# NinjaPCR-PowerSupply.net
KiCad netlist of a schematic drawn in EAGLE
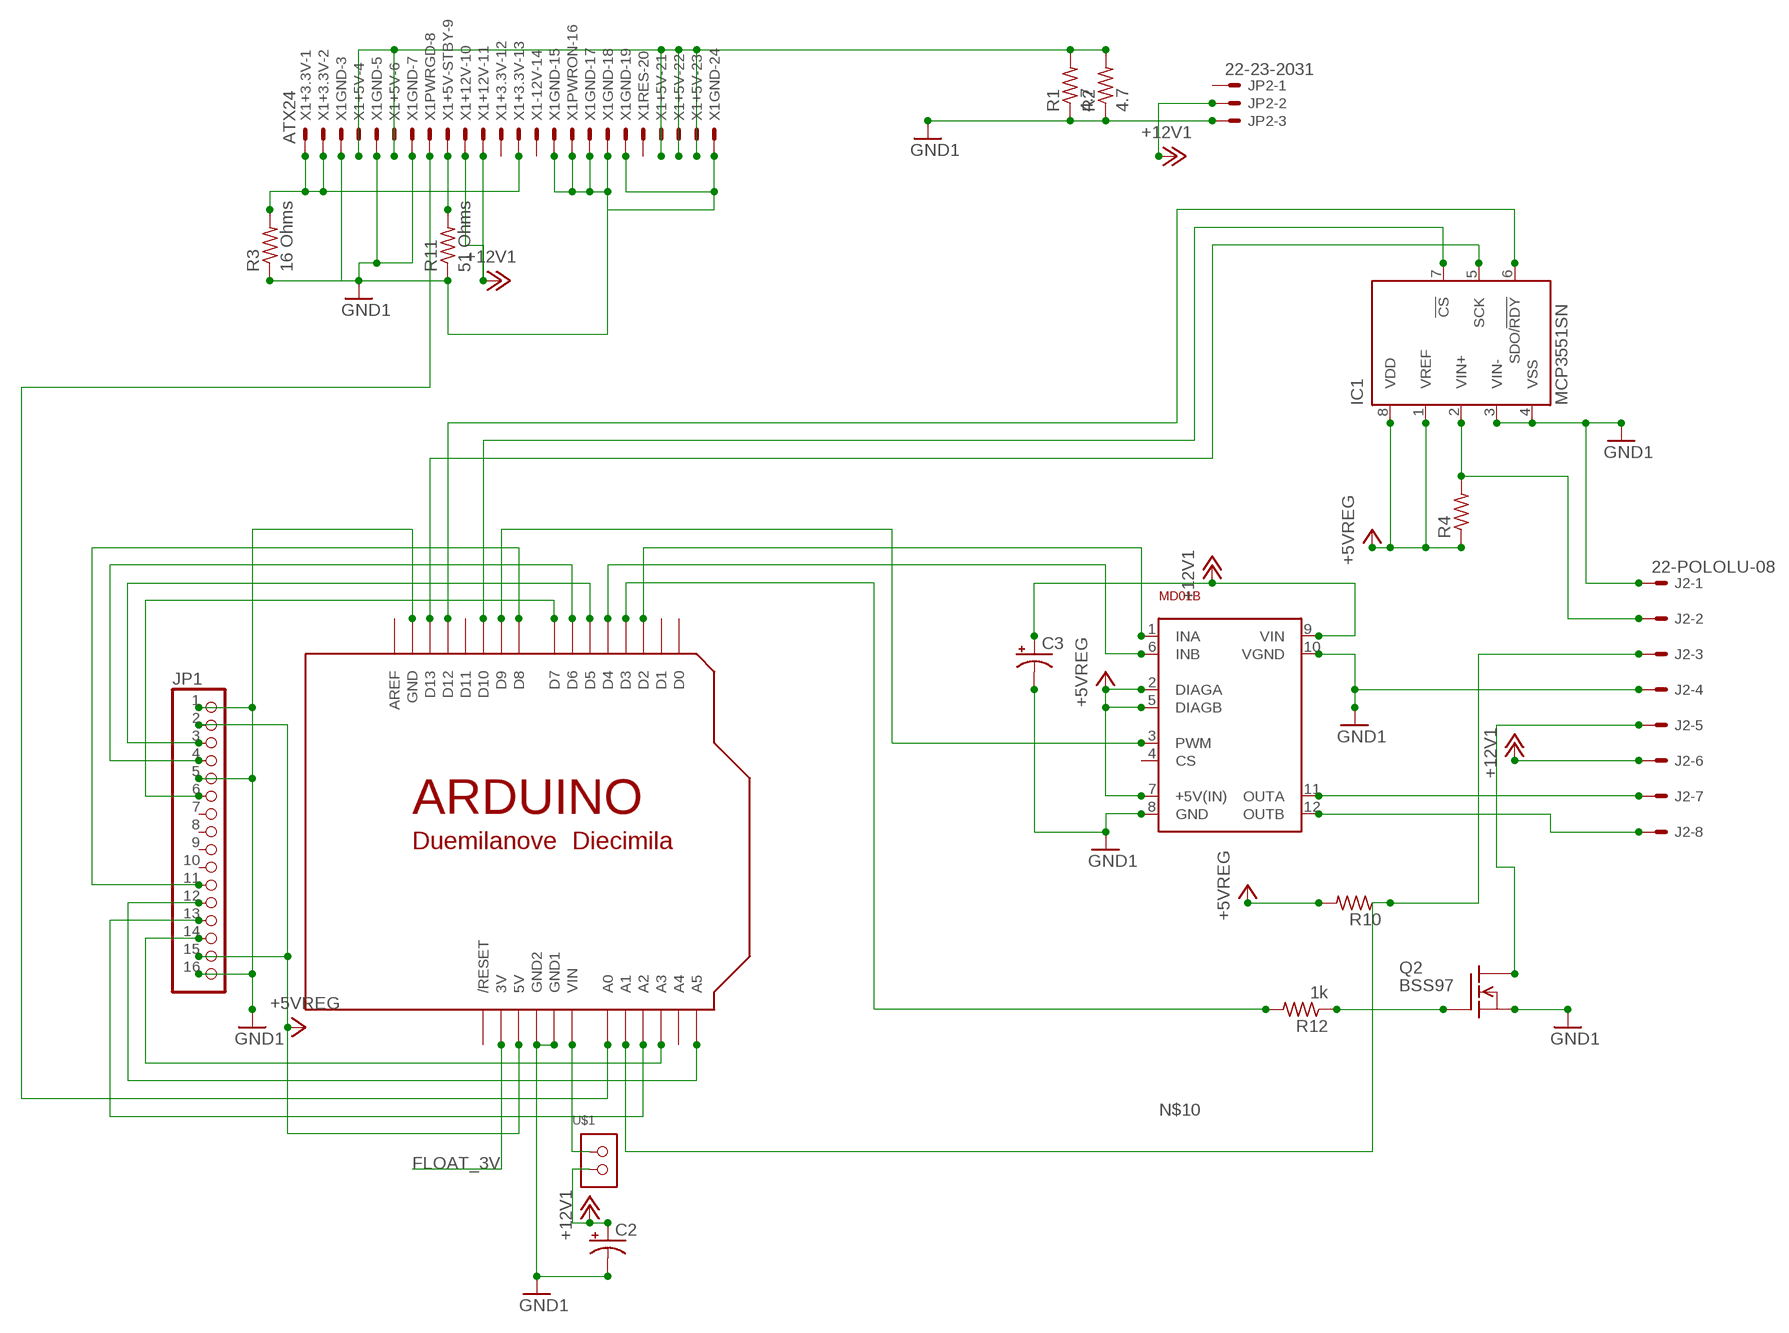
[diagram p0: schematic, sheet 1]

(export (version "E")
  (design (tool "Eeschema 10.0.6"))
  (components
    (comp (ref "C2")
      (value "CPOL-USE5-8.5")
      (footprint "eagle-import:E5-8,5")
      (libsource (lib "eagle-import") (part "CPOL-USE5-8.5"))
    )
    (comp (ref "C3")
      (value "CPOL-USE5-13")
      (footprint "eagle-import:E5-13")
      (libsource (lib "eagle-import") (part "CPOL-USE5-13"))
    )
    (comp (ref "IC1")
      (value "MCP3551SN")
      (footprint "eagle-import:SO-08")
      (fields (field (name "MPN") "MCP3551-E/SN"))
      (libsource (lib "eagle-import") (part "MCP355SN1"))
    )
    (comp (ref "J2")
      (value "22-POLOLU-08")
      (footprint "eagle-import:POLOLU-8")
      (libsource (lib "eagle-import") (part "22-?-08POLOLU"))
    )
    (comp (ref "JP1")
      (value "PINHD-1X16/90")
      (footprint "eagle-import:1X16_90")
      (libsource (lib "eagle-import") (part "PINHD-1X16/90"))
    )
    (comp (ref "JP2")
      (value "22-23-2031")
      (footprint "eagle-import:22-23-2031")
      (fields (field (name "MF") "MOLEX"))
      (libsource (lib "eagle-import") (part "22-23-2031"))
    )
    (comp (ref "MD01B")
      (value "VNH3SP30+4PIN")
      (footprint "eagle-import:VNH3SP30+4PIN")
      (libsource (lib "eagle-import") (part "VNH3SP30+4PIN"))
    )
    (comp (ref "Q2")
      (value "BSS97")
      (footprint "eagle-import:TO202")
      (libsource (lib "eagle-import") (part "BSS97"))
    )
    (comp (ref "R1")
      (value "4.7")
      (footprint "eagle-import:PR1")
      (libsource (lib "eagle-import") (part "PR1"))
    )
    (comp (ref "R2")
      (value "4.7")
      (footprint "eagle-import:PR1")
      (libsource (lib "eagle-import") (part "PR1"))
    )
    (comp (ref "R3")
      (value "16 Ohms")
      (footprint "eagle-import:0414_15")
      (libsource (lib "eagle-import") (part "resistor_R-US_0414/15"))
    )
    (comp (ref "R4")
      (value "R-US_0207/12")
      (footprint "eagle-import:0207_12")
      (libsource (lib "eagle-import") (part "resistor_R-US_0207/12"))
    )
    (comp (ref "R10")
      (value "R-US_0207/12")
      (footprint "eagle-import:0207_12")
      (libsource (lib "eagle-import") (part "resistor_R-US_0207/12"))
    )
    (comp (ref "R11")
      (value "51 Ohms")
      (footprint "eagle-import:0207_12")
      (libsource (lib "eagle-import") (part "R-US_0207/12"))
    )
    (comp (ref "R12")
      (value "1k")
      (footprint "eagle-import:0207_10")
      (libsource (lib "eagle-import") (part "resistor_R-US_0207/10"))
    )
    (comp (ref "U$1")
      (value "1X02")
      (footprint "eagle-import:1X02_1.1_UNSIGNED")
      (libsource (lib "eagle-import") (part "1X02"))
    )
    (comp (ref "U$3")
      (value "ARDUINODUEMILANOVE")
      (footprint "eagle-import:ARDUINO")
      (libsource (lib "eagle-import") (part "ARDUINODUEMILANOVE"))
    )
    (comp (ref "X1")
      (value "ATX24")
      (footprint "eagle-import:ATX24")
      (libsource (lib "eagle-import") (part "ATX24"))
    )
  )
  (nets
    (net (code "1") (name "+5VREG") (class "Default")
      (node (ref "IC1") (pin "1") (pinfunction "VREF_1") (pintype "input"))
      (node (ref "IC1") (pin "8") (pinfunction "VDD_8") (pintype "power_in"))
      (node (ref "JP1") (pin "15") (pinfunction "15_15") (pintype "passive"))
      (node (ref "JP1") (pin "2") (pinfunction "2_2") (pintype "passive"))
      (node (ref "MD01B") (pin "2") (pinfunction "DIAGA_2") (pintype "passive"))
      (node (ref "MD01B") (pin "5") (pinfunction "DIAGB_5") (pintype "passive"))
      (node (ref "MD01B") (pin "7") (pinfunction "+5V(IN)_7") (pintype "power_in"))
      (node (ref "R10") (pin "2") (pinfunction "2_2") (pintype "passive"))
      (node (ref "R4") (pin "1") (pinfunction "1_1") (pintype "passive"))
      (node (ref "U$3") (pin "5V") (pinfunction "5V_5V") (pintype "power_in"))
    )
    (net (code "2") (name "+12V1") (class "Default")
      (node (ref "C2") (pin "+") (pinfunction "+_+") (pintype "passive"))
      (node (ref "C3") (pin "+") (pinfunction "+_+") (pintype "passive"))
      (node (ref "J2") (pin "6") (pinfunction "S_6") (pintype "passive"))
      (node (ref "JP2") (pin "2") (pinfunction "S_2") (pintype "passive"))
      (node (ref "MD01B") (pin "9") (pinfunction "VIN_9") (pintype "power_in"))
      (node (ref "U$1") (pin "2") (pinfunction "2_2") (pintype "passive"))
      (node (ref "X1") (pin "10") (pinfunction "S_10") (pintype "passive"))
      (node (ref "X1") (pin "11") (pinfunction "S_11") (pintype "passive"))
    )
    (net (code "3") (name "/FLOAT_3V") (class "Default")
      (node (ref "U$3") (pin "3V") (pinfunction "3V_3V") (pintype "power_in"))
    )
    (net (code "4") (name "/N$10") (class "Default")
      (node (ref "JP1") (pin "13") (pinfunction "13_13") (pintype "passive"))
      (node (ref "U$3") (pin "A2") (pinfunction "A2_A2") (pintype "bidirectional"))
    )
    (net (code "5") (name "GND1") (class "Default")
      (node (ref "C2") (pin "-") (pinfunction "-_-") (pintype "passive"))
      (node (ref "C3") (pin "-") (pinfunction "-_-") (pintype "passive"))
      (node (ref "IC1") (pin "3") (pinfunction "VIN-_3") (pintype "input"))
      (node (ref "IC1") (pin "4") (pinfunction "VSS_4") (pintype "power_in"))
      (node (ref "J2") (pin "1") (pinfunction "S_1") (pintype "passive"))
      (node (ref "J2") (pin "4") (pinfunction "S_4") (pintype "passive"))
      (node (ref "JP1") (pin "1") (pinfunction "1_1") (pintype "passive"))
      (node (ref "JP1") (pin "16") (pinfunction "16_16") (pintype "passive"))
      (node (ref "JP1") (pin "5") (pinfunction "5_5") (pintype "passive"))
      (node (ref "JP2") (pin "3") (pinfunction "S_3") (pintype "passive"))
      (node (ref "MD01B") (pin "10") (pinfunction "VGND_10") (pintype "power_in"))
      (node (ref "MD01B") (pin "8") (pinfunction "GND_8") (pintype "power_in"))
      (node (ref "Q2") (pin "1") (pinfunction "S_1") (pintype "passive"))
      (node (ref "R1") (pin "1") (pinfunction "1_1") (pintype "passive"))
      (node (ref "R11") (pin "1") (pinfunction "1_1") (pintype "passive"))
      (node (ref "R2") (pin "1") (pinfunction "1_1") (pintype "passive"))
      (node (ref "R3") (pin "1") (pinfunction "1_1") (pintype "passive"))
      (node (ref "U$3") (pin "GND") (pinfunction "GND_GND") (pintype "power_in"))
      (node (ref "U$3") (pin "GND1") (pinfunction "GND1_GND1") (pintype "power_in"))
      (node (ref "U$3") (pin "GND2") (pinfunction "GND2_GND2") (pintype "power_in"))
      (node (ref "X1") (pin "15") (pinfunction "S_15") (pintype "passive"))
      (node (ref "X1") (pin "16") (pinfunction "S_16") (pintype "passive"))
      (node (ref "X1") (pin "17") (pinfunction "S_17") (pintype "passive"))
      (node (ref "X1") (pin "18") (pinfunction "S_18") (pintype "passive"))
      (node (ref "X1") (pin "19") (pinfunction "S_19") (pintype "passive"))
      (node (ref "X1") (pin "24") (pinfunction "S_24") (pintype "passive"))
      (node (ref "X1") (pin "3") (pinfunction "S_3") (pintype "passive"))
      (node (ref "X1") (pin "5") (pinfunction "S_5") (pintype "passive"))
      (node (ref "X1") (pin "7") (pinfunction "S_7") (pintype "passive"))
    )
    (net (code "6") (name "Net-(IC1-SCK)") (class "Default")
      (node (ref "IC1") (pin "5") (pinfunction "SCK_5") (pintype "input"))
      (node (ref "U$3") (pin "D13") (pinfunction "D13_D13") (pintype "bidirectional"))
    )
    (net (code "7") (name "Net-(IC1-SDO{slash}~{RDY})") (class "Default")
      (node (ref "IC1") (pin "6") (pinfunction "SDO/~{RDY}_6") (pintype "output"))
      (node (ref "U$3") (pin "D12") (pinfunction "D12_D12") (pintype "bidirectional"))
    )
    (net (code "8") (name "Net-(IC1-VIN+)") (class "Default")
      (node (ref "IC1") (pin "2") (pinfunction "VIN+_2") (pintype "input"))
      (node (ref "J2") (pin "2") (pinfunction "S_2") (pintype "passive"))
      (node (ref "R4") (pin "2") (pinfunction "2_2") (pintype "passive"))
    )
    (net (code "9") (name "Net-(IC1-~{CS})") (class "Default")
      (node (ref "IC1") (pin "7") (pinfunction "~{CS}_7") (pintype "input"))
      (node (ref "U$3") (pin "D10") (pinfunction "D10_D10") (pintype "bidirectional"))
    )
    (net (code "10") (name "Net-(J2C-S)") (class "Default")
      (node (ref "J2") (pin "3") (pinfunction "S_3") (pintype "passive"))
      (node (ref "R10") (pin "1") (pinfunction "1_1") (pintype "passive"))
      (node (ref "U$3") (pin "A1") (pinfunction "A1_A1") (pintype "bidirectional"))
    )
    (net (code "11") (name "Net-(J2E-S)") (class "Default")
      (node (ref "J2") (pin "5") (pinfunction "S_5") (pintype "passive"))
      (node (ref "Q2") (pin "2") (pinfunction "D_2") (pintype "passive"))
    )
    (net (code "12") (name "Net-(J2G-S)") (class "Default")
      (node (ref "J2") (pin "7") (pinfunction "S_7") (pintype "passive"))
      (node (ref "MD01B") (pin "11") (pinfunction "OUTA_11") (pintype "passive"))
    )
    (net (code "13") (name "Net-(J2H-S)") (class "Default")
      (node (ref "J2") (pin "8") (pinfunction "S_8") (pintype "passive"))
      (node (ref "MD01B") (pin "12") (pinfunction "OUTB_12") (pintype "passive"))
    )
    (net (code "14") (name "Net-(JP1-Pad3)") (class "Default")
      (node (ref "JP1") (pin "3") (pinfunction "3_3") (pintype "passive"))
      (node (ref "U$3") (pin "D5") (pinfunction "D5_D5") (pintype "bidirectional"))
    )
    (net (code "15") (name "Net-(JP1-Pad4)") (class "Default")
      (node (ref "JP1") (pin "4") (pinfunction "4_4") (pintype "passive"))
      (node (ref "U$3") (pin "D6") (pinfunction "D6_D6") (pintype "bidirectional"))
    )
    (net (code "16") (name "Net-(JP1-Pad6)") (class "Default")
      (node (ref "JP1") (pin "6") (pinfunction "6_6") (pintype "passive"))
      (node (ref "U$3") (pin "D7") (pinfunction "D7_D7") (pintype "bidirectional"))
    )
    (net (code "17") (name "Net-(JP1-Pad11)") (class "Default")
      (node (ref "JP1") (pin "11") (pinfunction "11_11") (pintype "passive"))
      (node (ref "U$3") (pin "D8") (pinfunction "D8_D8") (pintype "bidirectional"))
    )
    (net (code "18") (name "Net-(JP1-Pad12)") (class "Default")
      (node (ref "JP1") (pin "12") (pinfunction "12_12") (pintype "passive"))
      (node (ref "U$3") (pin "A5") (pinfunction "A5_A5") (pintype "bidirectional"))
    )
    (net (code "19") (name "Net-(JP1-Pad14)") (class "Default")
      (node (ref "JP1") (pin "14") (pinfunction "14_14") (pintype "passive"))
      (node (ref "U$3") (pin "A3") (pinfunction "A3_A3") (pintype "bidirectional"))
    )
    (net (code "20") (name "Net-(MD01B-INA)") (class "Default")
      (node (ref "MD01B") (pin "1") (pinfunction "INA_1") (pintype "passive"))
      (node (ref "U$3") (pin "D2") (pinfunction "D2_D2") (pintype "bidirectional"))
    )
    (net (code "21") (name "Net-(MD01B-INB)") (class "Default")
      (node (ref "MD01B") (pin "6") (pinfunction "INB_6") (pintype "passive"))
      (node (ref "U$3") (pin "D4") (pinfunction "D4_D4") (pintype "bidirectional"))
    )
    (net (code "22") (name "Net-(MD01B-PWM)") (class "Default")
      (node (ref "MD01B") (pin "3") (pinfunction "PWM_3") (pintype "passive"))
      (node (ref "U$3") (pin "D9") (pinfunction "D9_D9") (pintype "bidirectional"))
    )
    (net (code "23") (name "Net-(Q2-G)") (class "Default")
      (node (ref "Q2") (pin "3") (pinfunction "G_3") (pintype "passive"))
      (node (ref "R12") (pin "1") (pinfunction "1_1") (pintype "passive"))
    )
    (net (code "24") (name "Net-(R12-Pad2)") (class "Default")
      (node (ref "R12") (pin "2") (pinfunction "2_2") (pintype "passive"))
      (node (ref "U$3") (pin "D3") (pinfunction "D3_D3") (pintype "bidirectional"))
    )
    (net (code "25") (name "Net-(U$1-Pad1)") (class "Default")
      (node (ref "U$1") (pin "1") (pinfunction "1_1") (pintype "passive"))
      (node (ref "U$3") (pin "VIN") (pinfunction "VIN_VIN") (pintype "power_in"))
    )
    (net (code "26") (name "Net-(X1C-S)") (class "Default")
      (node (ref "R3") (pin "2") (pinfunction "2_2") (pintype "passive"))
      (node (ref "X1") (pin "1") (pinfunction "S_1") (pintype "passive"))
      (node (ref "X1") (pin "13") (pinfunction "S_13") (pintype "passive"))
      (node (ref "X1") (pin "2") (pinfunction "S_2") (pintype "passive"))
    )
    (net (code "27") (name "Net-(X1G-S)") (class "Default")
      (node (ref "R1") (pin "2") (pinfunction "2_2") (pintype "passive"))
      (node (ref "R2") (pin "2") (pinfunction "2_2") (pintype "passive"))
      (node (ref "X1") (pin "21") (pinfunction "S_21") (pintype "passive"))
      (node (ref "X1") (pin "22") (pinfunction "S_22") (pintype "passive"))
      (node (ref "X1") (pin "23") (pinfunction "S_23") (pintype "passive"))
      (node (ref "X1") (pin "4") (pinfunction "S_4") (pintype "passive"))
      (node (ref "X1") (pin "6") (pinfunction "S_6") (pintype "passive"))
    )
    (net (code "28") (name "Net-(X1L-S)") (class "Default")
      (node (ref "R11") (pin "2") (pinfunction "2_2") (pintype "passive"))
      (node (ref "X1") (pin "9") (pinfunction "S_9") (pintype "passive"))
    )
    (net (code "29") (name "Net-(X1V-S)") (class "Default")
      (node (ref "U$3") (pin "A0") (pinfunction "A0_A0") (pintype "bidirectional"))
      (node (ref "X1") (pin "8") (pinfunction "S_8") (pintype "passive"))
    )
    (net (code "30") (name "unconnected-(JP1-Pad7)") (class "Default")
      (node (ref "JP1") (pin "7") (pinfunction "7_7") (pintype "passive"))
    )
    (net (code "31") (name "unconnected-(JP1-Pad8)") (class "Default")
      (node (ref "JP1") (pin "8") (pinfunction "8_8") (pintype "passive"))
    )
    (net (code "32") (name "unconnected-(JP1-Pad9)") (class "Default")
      (node (ref "JP1") (pin "9") (pinfunction "9_9") (pintype "passive"))
    )
    (net (code "33") (name "unconnected-(JP1-Pad10)") (class "Default")
      (node (ref "JP1") (pin "10") (pinfunction "10_10") (pintype "passive"))
    )
    (net (code "34") (name "unconnected-(JP2A-S-Pad1)") (class "Default")
      (node (ref "JP2") (pin "1") (pinfunction "S_1") (pintype "passive"))
    )
    (net (code "35") (name "unconnected-(MD01B-CS-Pad4)") (class "Default")
      (node (ref "MD01B") (pin "4") (pinfunction "CS_4") (pintype "passive"))
    )
    (net (code "36") (name "unconnected-(U$3-PadA4)") (class "Default")
      (node (ref "U$3") (pin "A4") (pinfunction "A4_A4") (pintype "bidirectional"))
    )
    (net (code "37") (name "unconnected-(U$3-PadAREF)") (class "Default")
      (node (ref "U$3") (pin "AREF") (pinfunction "AREF_AREF") (pintype "bidirectional"))
    )
    (net (code "38") (name "unconnected-(U$3-PadD0)") (class "Default")
      (node (ref "U$3") (pin "D0") (pinfunction "D0_D0") (pintype "bidirectional"))
    )
    (net (code "39") (name "unconnected-(U$3-PadD1)") (class "Default")
      (node (ref "U$3") (pin "D1") (pinfunction "D1_D1") (pintype "bidirectional"))
    )
    (net (code "40") (name "unconnected-(U$3-PadD11)") (class "Default")
      (node (ref "U$3") (pin "D11") (pinfunction "D11_D11") (pintype "bidirectional"))
    )
    (net (code "41") (name "unconnected-(U$3-{slash}RESET-PadRESET)") (class "Default")
      (node (ref "U$3") (pin "RESET") (pinfunction "/RESET_RESET") (pintype "bidirectional"))
    )
    (net (code "42") (name "unconnected-(X1D-S-Pad12)") (class "Default")
      (node (ref "X1") (pin "12") (pinfunction "S_12") (pintype "passive"))
    )
    (net (code "43") (name "unconnected-(X1M-S-Pad14)") (class "Default")
      (node (ref "X1") (pin "14") (pinfunction "S_14") (pintype "passive"))
    )
    (net (code "44") (name "unconnected-(X1X-S-Pad20)") (class "Default")
      (node (ref "X1") (pin "20") (pinfunction "S_20") (pintype "passive"))
    )
  )
)
